# Evaporometer_OnePiece.net
KiCad netlist of a schematic drawn in EAGLE
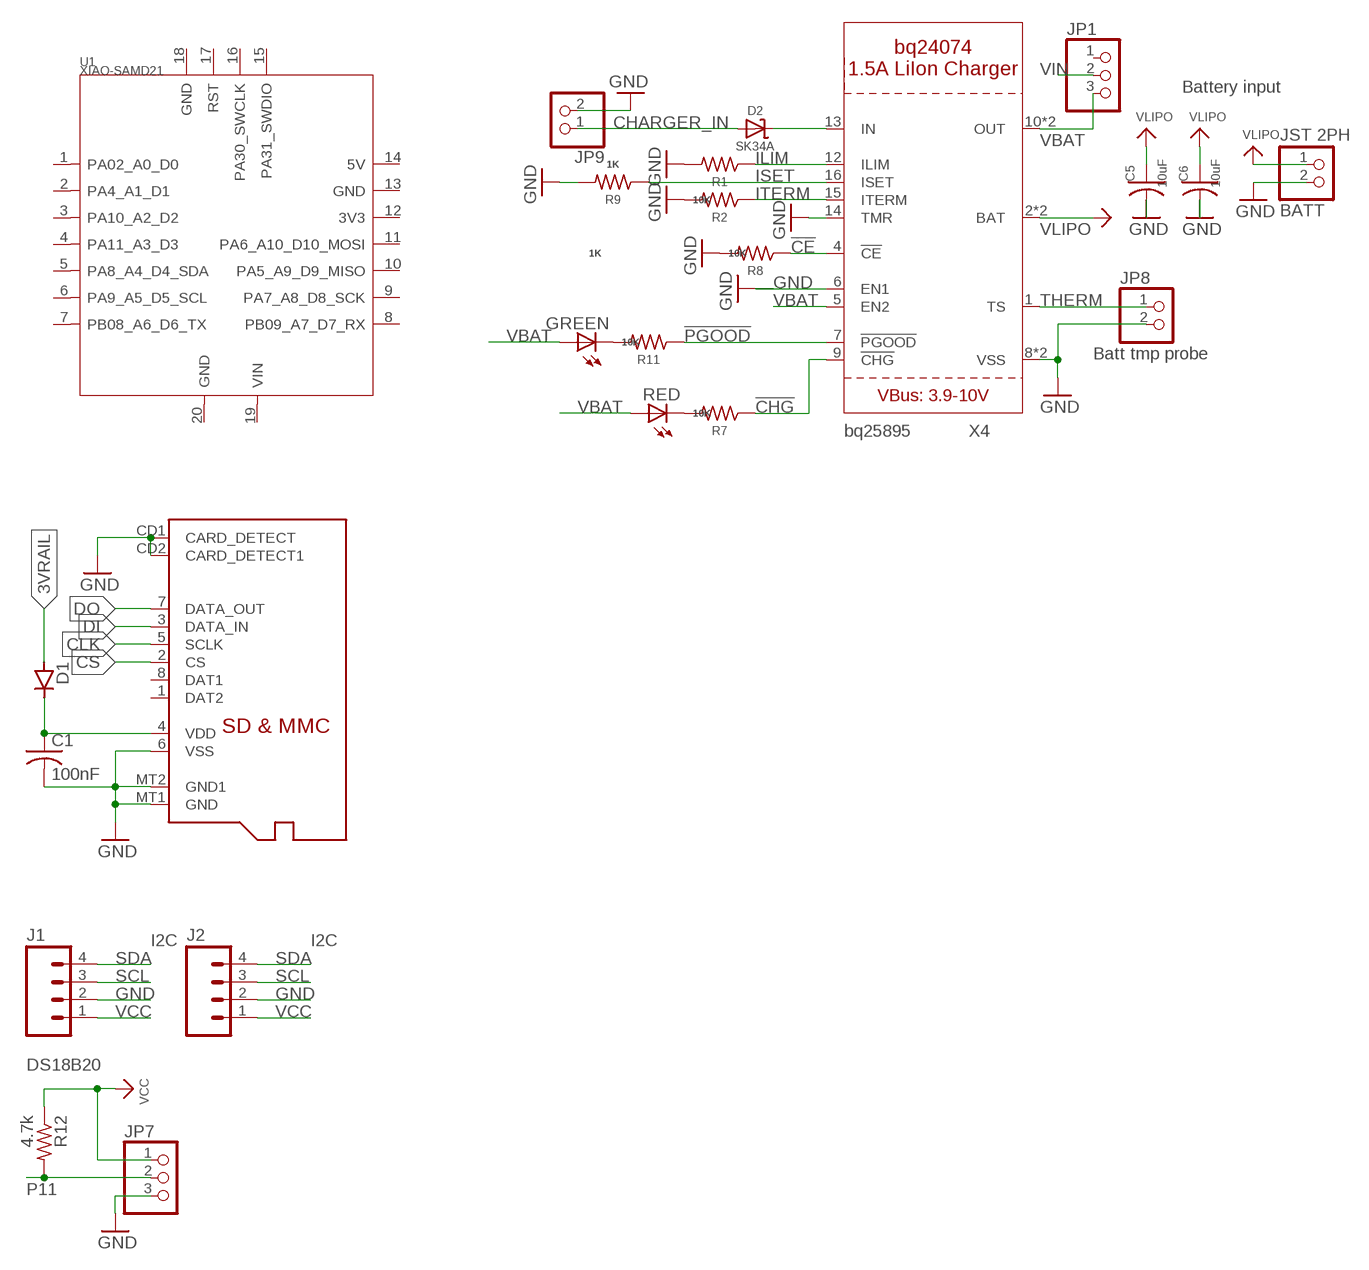
[diagram p0: schematic, sheet 1, part 1 of 2]
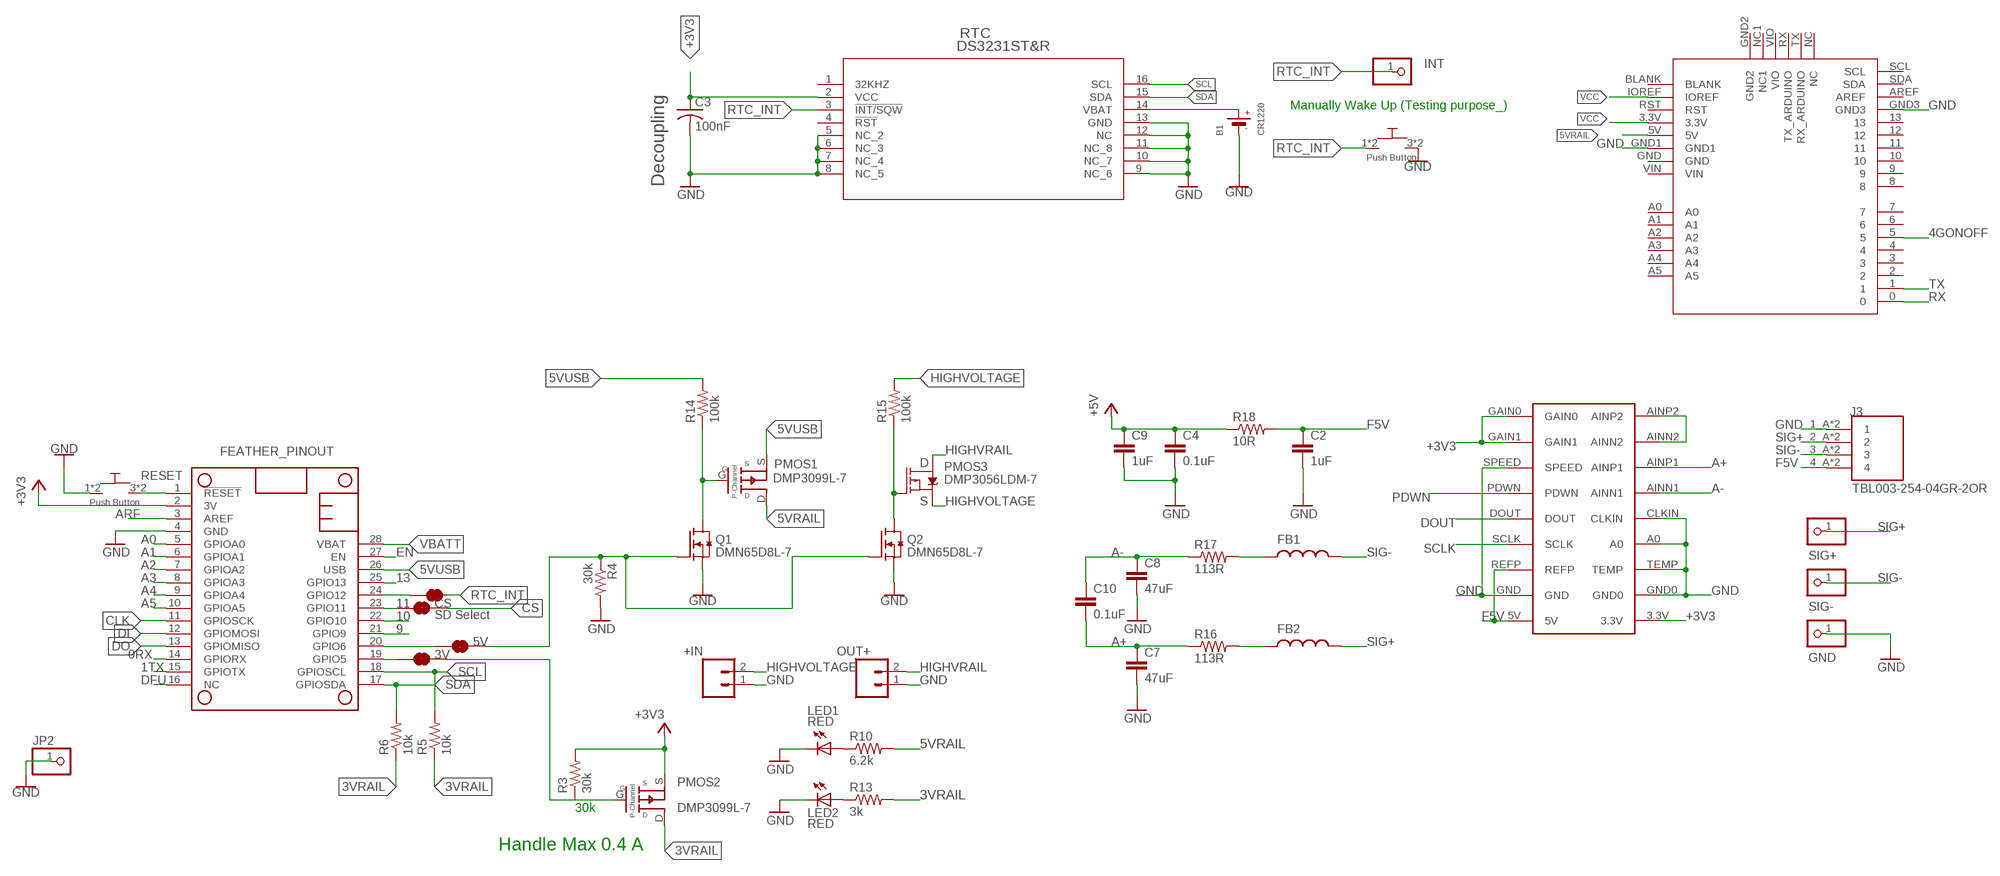
[diagram p1: schematic, sheet 1, part 2 of 2]

(export (version "E")
  (design (tool "Eeschema 10.0.6"))
  (components
    (comp (ref "+IN")
      (value "HIGHV-IN")
      (footprint "eagle-import:1X02_NO_SILK")
      (libsource (lib "eagle-import") (part "CONN_021X02_NO_SILK"))
    )
    (comp (ref "3V")
      (value "JUMPER-SMT_2_NC_TRACE_SILK")
      (footprint "eagle-import:SMT-JUMPER_2_NC_TRACE_SILK")
      (libsource (lib "eagle-import") (part "JUMPER-SMT_2_NC_TRACE_SILK"))
    )
    (comp (ref "5V")
      (value "JUMPER-SMT_2_NC_TRACE_SILK")
      (footprint "eagle-import:SMT-JUMPER_2_NC_TRACE_SILK")
      (libsource (lib "eagle-import") (part "JUMPER-SMT_2_NC_TRACE_SILK"))
    )
    (comp (ref "ADS1232")
      (value "ADS1232")
      (footprint "eagle-import:ADS1232")
      (libsource (lib "eagle-import") (part "ADS1232"))
    )
    (comp (ref "B1")
      (value "CR1220")
      (footprint "eagle-import:CR1220")
      (libsource (lib "eagle-import") (part "BATTERYCR1220_SMT"))
    )
    (comp (ref "BATT")
      (value "JST 2PH")
      (footprint "eagle-import:JST-PH-2-SMT-RA")
      (libsource (lib "eagle-import") (part "JST_2PIN-SMT-RA"))
    )
    (comp (ref "C1")
      (value "100nF")
      (footprint "eagle-import:C1206")
      (libsource (lib "eagle-import") (part "C-USC1206"))
    )
    (comp (ref "C2")
      (value "1uF")
      (footprint "eagle-import:C0805")
      (libsource (lib "eagle-import") (part "C-EUC0805"))
    )
    (comp (ref "C3")
      (value "100nF")
      (footprint "eagle-import:C1206")
      (libsource (lib "eagle-import") (part "C-USC1206"))
    )
    (comp (ref "C4")
      (value "0.1uF")
      (footprint "eagle-import:C0805")
      (libsource (lib "eagle-import") (part "C-EUC0805"))
    )
    (comp (ref "C5")
      (value "10uF")
      (footprint "eagle-import:C0805K")
      (libsource (lib "eagle-import") (part "C-USC0805K"))
    )
    (comp (ref "C6")
      (value "10uF")
      (footprint "eagle-import:C0805K")
      (libsource (lib "eagle-import") (part "C-USC0805K"))
    )
    (comp (ref "C7")
      (value "47uF")
      (footprint "eagle-import:C0805")
      (libsource (lib "eagle-import") (part "C-EUC0805"))
    )
    (comp (ref "C8")
      (value "47uF")
      (footprint "eagle-import:C0805")
      (libsource (lib "eagle-import") (part "C-EUC0805"))
    )
    (comp (ref "C9")
      (value "1uF")
      (footprint "eagle-import:C0805")
      (libsource (lib "eagle-import") (part "C-EUC0805"))
    )
    (comp (ref "C10")
      (value "0.1uF")
      (footprint "eagle-import:C0805")
      (libsource (lib "eagle-import") (part "C-EUC0805"))
    )
    (comp (ref "CS")
      (value "SD Select")
      (footprint "eagle-import:SMT-JUMPER_2_NC_TRACE_SILK")
      (libsource (lib "eagle-import") (part "JUMPER-SMT_2_NC_TRACE_SILK"))
    )
    (comp (ref "D1")
      (value "D-SOD123")
      (footprint "eagle-import:SOD123")
      (libsource (lib "eagle-import") (part "D-SOD123"))
    )
    (comp (ref "D2")
      (value "SK34A")
      (footprint "eagle-import:SMADIODE")
      (libsource (lib "eagle-import") (part "DIODE-SCHOTTKYSMA"))
    )
    (comp (ref "FB1")
      (value "WE-RFI_0805A_744760282A")
      (footprint "eagle-import:WE-RFI_0805A")
      (libsource (lib "eagle-import") (part "WE-RFI_0805A_744760282A"))
    )
    (comp (ref "FB2")
      (value "WE-RFI_0805A_744760282A")
      (footprint "eagle-import:WE-RFI_0805A")
      (libsource (lib "eagle-import") (part "WE-RFI_0805A_744760282A"))
    )
    (comp (ref "GND")
      (value "PINHD-1X1")
      (footprint "eagle-import:1X01")
      (libsource (lib "eagle-import") (part "pinhead_325_PINHD-1X1"))
    )
    (comp (ref "GREEN")
      (value "LEDSMT1206")
      (footprint "eagle-import:1206")
      (libsource (lib "eagle-import") (part "adafruit_420_LEDSMT1206"))
    )
    (comp (ref "INT")
      (value "PINHD-1X1CB")
      (footprint "eagle-import:1X01-CLEANBIG")
      (libsource (lib "eagle-import") (part "PINHD-1X1CB"))
    )
    (comp (ref "J1")
      (value "M04PTH")
      (footprint "eagle-import:1X04")
      (libsource (lib "eagle-import") (part "M04PTH"))
    )
    (comp (ref "J2")
      (value "M04PTH")
      (footprint "eagle-import:1X04")
      (libsource (lib "eagle-import") (part "M04PTH"))
    )
    (comp (ref "J3")
      (value "TBL003-254-04GR-2OR")
      (footprint "eagle-import:CUI_TBL003-254-04GR-2OR")
      (fields (field (name "MF") "CUI Devices"))
      (libsource (lib "eagle-import") (part "TBL003-254-04GR-2OR"))
    )
    (comp (ref "JP1")
      (value "PINHD-1X3")
      (footprint "eagle-import:1X03")
      (libsource (lib "eagle-import") (part "PINHD-1X3"))
    )
    (comp (ref "JP2")
      (value "PINHD-1X1CB")
      (footprint "eagle-import:1X01-CLEANBIG")
      (libsource (lib "eagle-import") (part "PINHD-1X1CB"))
    )
    (comp (ref "JP7")
      (value "PINHD-1X3")
      (footprint "eagle-import:1X03")
      (libsource (lib "eagle-import") (part "PINHD-1X3"))
    )
    (comp (ref "JP8")
      (value "PINHD-1X2")
      (footprint "eagle-import:1X02")
      (libsource (lib "eagle-import") (part "PINHD-1X2"))
    )
    (comp (ref "JP9")
      (value "PINHD-1X2")
      (footprint "eagle-import:1X02")
      (libsource (lib "eagle-import") (part "PINHD-1X2"))
    )
    (comp (ref "LED1")
      (value "RED")
      (footprint "eagle-import:CHIPLED_0805")
      (libsource (lib "eagle-import") (part "LEDCHIPLED_0805"))
    )
    (comp (ref "LED2")
      (value "RED")
      (footprint "eagle-import:CHIPLED_0805")
      (libsource (lib "eagle-import") (part "LEDCHIPLED_0805"))
    )
    (comp (ref "MICROSD")
      (value "MICROSD")
      (footprint "eagle-import:MICROSD")
      (libsource (lib "eagle-import") (part "MICROSD"))
    )
    (comp (ref "MS2")
      (value "FEATHER_PINOUT")
      (footprint "eagle-import:FEATHERWING")
      (libsource (lib "eagle-import") (part "FEATHERWING"))
    )
    (comp (ref "OUT+")
      (value "HIGHV-OUT")
      (footprint "eagle-import:1X02_NO_SILK")
      (libsource (lib "eagle-import") (part "CONN_021X02_NO_SILK"))
    )
    (comp (ref "PMOS1")
      (value "DMP3099L-7")
      (footprint "eagle-import:SOT-23-3")
      (libsource (lib "eagle-import") (part "SSM3J3228R"))
    )
    (comp (ref "PMOS2")
      (value "DMP3099L-7")
      (footprint "eagle-import:SOT-23-3")
      (libsource (lib "eagle-import") (part "SSM3J3228R"))
    )
    (comp (ref "PMOS3")
      (value "DMP3056LDM-7")
      (footprint "eagle-import:SOT23-6")
      (libsource (lib "eagle-import") (part "P-MOSFET"))
    )
    (comp (ref "Q1")
      (value "DMN65D8L-7")
      (footprint "eagle-import:SOT23-S")
      (libsource (lib "eagle-import") (part "NMOS"))
    )
    (comp (ref "Q2")
      (value "DMN65D8L-7")
      (footprint "eagle-import:SOT23-S")
      (libsource (lib "eagle-import") (part "NMOS"))
    )
    (comp (ref "R1")
      (value "1K")
      (footprint "eagle-import:M0805")
      (libsource (lib "eagle-import") (part "R-US_M0805"))
    )
    (comp (ref "R2")
      (value "10K")
      (footprint "eagle-import:M0805")
      (libsource (lib "eagle-import") (part "R-US_M0805"))
    )
    (comp (ref "R3")
      (value "30k")
      (footprint "eagle-import:RES_1206")
      (fields
        (field (name "DIGIKEY_PART_NUMBER") "WSLP-.05TR-ND")
        (field (name "MANUFACTURER") "Vishay Dale")
        (field (name "MPN") "WSLP1206R0500FEA")
        (field (name "CREATED_BY") "PCBLayout.com")
      )
      (libsource (lib "eagle-import") (part "WSLP1206R0500FEA"))
    )
    (comp (ref "R4")
      (value "30k")
      (footprint "eagle-import:RES_1206")
      (fields
        (field (name "DIGIKEY_PART_NUMBER") "WSLP-.05TR-ND")
        (field (name "MANUFACTURER") "Vishay Dale")
        (field (name "MPN") "WSLP1206R0500FEA")
        (field (name "CREATED_BY") "PCBLayout.com")
      )
      (libsource (lib "eagle-import") (part "WSLP1206R0500FEA"))
    )
    (comp (ref "R5")
      (value "10k")
      (footprint "eagle-import:RES_1206")
      (fields
        (field (name "DIGIKEY_PART_NUMBER") "WSLP-.05TR-ND")
        (field (name "MANUFACTURER") "Vishay Dale")
        (field (name "MPN") "WSLP1206R0500FEA")
        (field (name "CREATED_BY") "PCBLayout.com")
      )
      (libsource (lib "eagle-import") (part "WSLP1206R0500FEA"))
    )
    (comp (ref "R6")
      (value "10k")
      (footprint "eagle-import:RES_1206")
      (fields
        (field (name "DIGIKEY_PART_NUMBER") "WSLP-.05TR-ND")
        (field (name "MANUFACTURER") "Vishay Dale")
        (field (name "MPN") "WSLP1206R0500FEA")
        (field (name "CREATED_BY") "PCBLayout.com")
      )
      (libsource (lib "eagle-import") (part "WSLP1206R0500FEA"))
    )
    (comp (ref "R7")
      (value "10K")
      (footprint "eagle-import:M0805")
      (libsource (lib "eagle-import") (part "R-US_M0805"))
    )
    (comp (ref "R8")
      (value "10K")
      (footprint "eagle-import:M0805")
      (libsource (lib "eagle-import") (part "R-US_M0805"))
    )
    (comp (ref "R9")
      (value "1K")
      (footprint "eagle-import:M0805")
      (libsource (lib "eagle-import") (part "R-US_M0805"))
    )
    (comp (ref "R10")
      (value "6.2k")
      (footprint "eagle-import:RES_1206")
      (fields
        (field (name "DIGIKEY_PART_NUMBER") "WSLP-.05TR-ND")
        (field (name "MANUFACTURER") "Vishay Dale")
        (field (name "MPN") "WSLP1206R0500FEA")
        (field (name "CREATED_BY") "PCBLayout.com")
      )
      (libsource (lib "eagle-import") (part "WSLP1206R0500FEA"))
    )
    (comp (ref "R11")
      (value "10K")
      (footprint "eagle-import:M0805")
      (libsource (lib "eagle-import") (part "R-US_M0805"))
    )
    (comp (ref "R12")
      (value "4.7k")
      (footprint "eagle-import:0805-THM")
      (libsource (lib "eagle-import") (part "FLIPFLOP-RES"))
    )
    (comp (ref "R13")
      (value "3k")
      (footprint "eagle-import:RES_1206")
      (fields
        (field (name "DIGIKEY_PART_NUMBER") "WSLP-.05TR-ND")
        (field (name "MANUFACTURER") "Vishay Dale")
        (field (name "MPN") "WSLP1206R0500FEA")
        (field (name "CREATED_BY") "PCBLayout.com")
      )
      (libsource (lib "eagle-import") (part "WSLP1206R0500FEA"))
    )
    (comp (ref "R14")
      (value "100k")
      (footprint "eagle-import:RES_1206")
      (fields
        (field (name "DIGIKEY_PART_NUMBER") "WSLP-.05TR-ND")
        (field (name "MANUFACTURER") "Vishay Dale")
        (field (name "MPN") "WSLP1206R0500FEA")
        (field (name "CREATED_BY") "PCBLayout.com")
      )
      (libsource (lib "eagle-import") (part "WSLP1206R0500FEA"))
    )
    (comp (ref "R15")
      (value "100k")
      (footprint "eagle-import:RES_1206")
      (fields
        (field (name "DIGIKEY_PART_NUMBER") "WSLP-.05TR-ND")
        (field (name "MANUFACTURER") "Vishay Dale")
        (field (name "MPN") "WSLP1206R0500FEA")
        (field (name "CREATED_BY") "PCBLayout.com")
      )
      (libsource (lib "eagle-import") (part "WSLP1206R0500FEA"))
    )
    (comp (ref "R16")
      (value "113R")
      (footprint "eagle-import:R0805")
      (libsource (lib "eagle-import") (part "rcl_334_R-US_R0805"))
    )
    (comp (ref "R17")
      (value "113R")
      (footprint "eagle-import:R0805")
      (libsource (lib "eagle-import") (part "rcl_334_R-US_R0805"))
    )
    (comp (ref "R18")
      (value "10R")
      (footprint "eagle-import:R0805")
      (libsource (lib "eagle-import") (part "rcl_334_R-US_R0805"))
    )
    (comp (ref "RED")
      (value "LEDSMT1206")
      (footprint "eagle-import:1206")
      (libsource (lib "eagle-import") (part "adafruit_420_LEDSMT1206"))
    )
    (comp (ref "RTC")
      (value "DS3231ST&R")
      (footprint "eagle-import:21-0042B_16")
      (fields (field (name "MANUFACTURER_PART_NUMBER") "DS3231S#T&R"))
      (libsource (lib "eagle-import") (part "DS3231ST&R"))
    )
    (comp (ref "RTC_INT")
      (value "JUMPER-SMT_2_NC_TRACE_SILK")
      (footprint "eagle-import:SMT-JUMPER_2_NC_TRACE_SILK")
      (libsource (lib "eagle-import") (part "JUMPER-SMT_2_NC_TRACE_SILK"))
    )
    (comp (ref "SIG+")
      (value "PINHD-1X1")
      (footprint "eagle-import:1X01")
      (libsource (lib "eagle-import") (part "pinhead_325_PINHD-1X1"))
    )
    (comp (ref "SIG-")
      (value "PINHD-1X1")
      (footprint "eagle-import:1X01")
      (libsource (lib "eagle-import") (part "pinhead_325_PINHD-1X1"))
    )
    (comp (ref "U$1")
      (value "PUSH_BUTTON")
      (footprint "eagle-import:PUSHBUTTON_SMD")
      (libsource (lib "eagle-import") (part "PUSH_BUTTON"))
    )
    (comp (ref "U$2")
      (value "LTE_BOARD")
      (footprint "eagle-import:LTE_BOARD_FOOTPRINT")
      (libsource (lib "eagle-import") (part "LTE_BOARD"))
    )
    (comp (ref "U$3")
      (value "PUSH_BUTTON")
      (footprint "eagle-import:PUSHBUTTON_SMD")
      (libsource (lib "eagle-import") (part "PUSH_BUTTON"))
    )
    (comp (ref "U1")
      (value "XIAO-SAMD21")
      (footprint "eagle-import:XIAO-SAMD21_RP2040-MODULE14P-2.54-21X17.8MM")
      (libsource (lib "eagle-import") (part "XIAO-SAMD21"))
    )
    (comp (ref "X4")
      (value "BQ24074")
      (footprint "eagle-import:QFN16_3MM")
      (libsource (lib "eagle-import") (part "BQ24074"))
    )
  )
  (nets
    (net (code "1") (name "+3V3") (class "Default")
      (node (ref "ADS1232") (pin "3.3V") (pinfunction "3.3V_3.3V") (pintype "bidirectional"))
      (node (ref "ADS1232") (pin "GAIN0") (pinfunction "GAIN0_GAIN0") (pintype "bidirectional"))
      (node (ref "ADS1232") (pin "GAIN1") (pinfunction "GAIN1_GAIN1") (pintype "bidirectional"))
      (node (ref "C3") (pin "1") (pinfunction "1_1") (pintype "passive"))
      (node (ref "MS2") (pin "2") (pinfunction "3V_2") (pintype "power_in"))
      (node (ref "PMOS2") (pin "S") (pinfunction "S_S") (pintype "bidirectional"))
      (node (ref "R3") (pin "2") (pinfunction "2_2") (pintype "passive"))
      (node (ref "RTC") (pin "2") (pinfunction "VCC_2") (pintype "power_in"))
    )
    (net (code "2") (name "+5V") (class "Default")
      (node (ref "C4") (pin "1") (pinfunction "1_1") (pintype "passive"))
      (node (ref "C9") (pin "1") (pinfunction "1_1") (pintype "passive"))
      (node (ref "R18") (pin "1") (pinfunction "1_1") (pintype "passive"))
    )
    (net (code "3") (name "/0RX") (class "Default")
      (node (ref "MS2") (pin "14") (pinfunction "GPIORX_14") (pintype "bidirectional"))
    )
    (net (code "4") (name "/1TX") (class "Default")
      (node (ref "MS2") (pin "15") (pinfunction "GPIOTX_15") (pintype "bidirectional"))
    )
    (net (code "5") (name "/4GONOFF") (class "Default")
      (node (ref "U$2") (pin "5") (pinfunction "5_5") (pintype "bidirectional"))
    )
    (net (code "6") (name "/9") (class "Default")
      (node (ref "MS2") (pin "21") (pinfunction "GPIO9_21") (pintype "bidirectional"))
    )
    (net (code "7") (name "/10") (class "Default")
      (node (ref "MS2") (pin "22") (pinfunction "GPIO10_22") (pintype "bidirectional"))
    )
    (net (code "8") (name "/11") (class "Default")
      (node (ref "CS") (pin "1") (pinfunction "1_1") (pintype "passive"))
      (node (ref "MS2") (pin "23") (pinfunction "GPIO11_23") (pintype "bidirectional"))
    )
    (net (code "9") (name "/13") (class "Default")
      (node (ref "MS2") (pin "25") (pinfunction "GPIO13_25") (pintype "bidirectional"))
    )
    (net (code "10") (name "/A+") (class "Default")
      (node (ref "ADS1232") (pin "AINP1") (pinfunction "AINP1_AINP1") (pintype "bidirectional"))
      (node (ref "C10") (pin "2") (pinfunction "2_2") (pintype "passive"))
      (node (ref "C7") (pin "1") (pinfunction "1_1") (pintype "passive"))
      (node (ref "R16") (pin "1") (pinfunction "1_1") (pintype "passive"))
    )
    (net (code "11") (name "/A-") (class "Default")
      (node (ref "ADS1232") (pin "AINN1") (pinfunction "AINN1_AINN1") (pintype "bidirectional"))
      (node (ref "C10") (pin "1") (pinfunction "1_1") (pintype "passive"))
      (node (ref "C8") (pin "1") (pinfunction "1_1") (pintype "passive"))
      (node (ref "R17") (pin "1") (pinfunction "1_1") (pintype "passive"))
    )
    (net (code "12") (name "/A0") (class "Default")
      (node (ref "MS2") (pin "5") (pinfunction "GPIOA0_5") (pintype "bidirectional"))
    )
    (net (code "13") (name "/A1") (class "Default")
      (node (ref "MS2") (pin "6") (pinfunction "GPIOA1_6") (pintype "bidirectional"))
    )
    (net (code "14") (name "/A2") (class "Default")
      (node (ref "MS2") (pin "7") (pinfunction "GPIOA2_7") (pintype "bidirectional"))
    )
    (net (code "15") (name "/A3") (class "Default")
      (node (ref "MS2") (pin "8") (pinfunction "GPIOA3_8") (pintype "bidirectional"))
    )
    (net (code "16") (name "/A4") (class "Default")
      (node (ref "MS2") (pin "9") (pinfunction "GPIOA4_9") (pintype "bidirectional"))
    )
    (net (code "17") (name "/A5") (class "Default")
      (node (ref "MS2") (pin "10") (pinfunction "GPIOA5_10") (pintype "bidirectional"))
    )
    (net (code "18") (name "/ARF") (class "Default")
      (node (ref "MS2") (pin "3") (pinfunction "AREF_3") (pintype "passive"))
    )
    (net (code "19") (name "/CHARGER_IN") (class "Default")
      (node (ref "D2") (pin "A") (pinfunction "A_A") (pintype "passive"))
      (node (ref "JP9") (pin "1") (pinfunction "1_1") (pintype "passive"))
    )
    (net (code "20") (name "/DFU") (class "Default")
      (node (ref "MS2") (pin "16") (pinfunction "NC_16") (pintype "passive"))
    )
    (net (code "21") (name "/DOUT") (class "Default")
      (node (ref "ADS1232") (pin "DOUT") (pinfunction "DOUT_DOUT") (pintype "bidirectional"))
    )
    (net (code "22") (name "/EN") (class "Default")
      (node (ref "MS2") (pin "27") (pinfunction "EN_27") (pintype "passive"))
    )
    (net (code "23") (name "/F5V") (class "Default")
      (node (ref "ADS1232") (pin "5V") (pinfunction "5V_5V") (pintype "bidirectional"))
      (node (ref "ADS1232") (pin "REFP") (pinfunction "REFP_REFP") (pintype "bidirectional"))
      (node (ref "C2") (pin "1") (pinfunction "1_1") (pintype "passive"))
      (node (ref "J3") (pin "4_A") (pinfunction "4_4_A") (pintype "passive"))
      (node (ref "J3") (pin "4_B") (pinfunction "4_4_B") (pintype "passive"))
      (node (ref "R18") (pin "2") (pinfunction "2_2") (pintype "passive"))
    )
    (net (code "24") (name "/HIGHVRAIL") (class "Default")
      (node (ref "OUT+") (pin "2") (pinfunction "2_2") (pintype "passive"))
      (node (ref "PMOS3") (pin "1") (pinfunction "D_1") (pintype "bidirectional"))
      (node (ref "PMOS3") (pin "2") (pinfunction "D_2") (pintype "bidirectional"))
      (node (ref "PMOS3") (pin "5") (pinfunction "D_5") (pintype "bidirectional"))
      (node (ref "PMOS3") (pin "6") (pinfunction "D_6") (pintype "bidirectional"))
    )
    (net (code "25") (name "/ILIM") (class "Default")
      (node (ref "R1") (pin "1") (pinfunction "1_1") (pintype "passive"))
      (node (ref "X4") (pin "12") (pinfunction "ILIM_12") (pintype "input"))
    )
    (net (code "26") (name "/ISET") (class "Default")
      (node (ref "R9") (pin "1") (pinfunction "1_1") (pintype "passive"))
      (node (ref "X4") (pin "16") (pinfunction "ISET_16") (pintype "input"))
    )
    (net (code "27") (name "/ITERM") (class "Default")
      (node (ref "R2") (pin "1") (pinfunction "1_1") (pintype "passive"))
      (node (ref "X4") (pin "15") (pinfunction "ITERM_15") (pintype "input"))
    )
    (net (code "28") (name "/P11") (class "Default")
      (node (ref "JP7") (pin "2") (pinfunction "2_2") (pintype "passive"))
      (node (ref "R12") (pin "2") (pinfunction "2_2") (pintype "passive"))
    )
    (net (code "29") (name "/PDWN") (class "Default")
      (node (ref "ADS1232") (pin "PDWN") (pinfunction "PDWN_PDWN") (pintype "bidirectional"))
    )
    (net (code "30") (name "/RESET") (class "Default")
      (node (ref "MS2") (pin "1") (pinfunction "~{RESET}_1") (pintype "input"))
      (node (ref "U$3") (pin "3") (pinfunction "P$2_3") (pintype "bidirectional"))
      (node (ref "U$3") (pin "4") (pinfunction "P$2_4") (pintype "bidirectional"))
    )
    (net (code "31") (name "/RX") (class "Default")
      (node (ref "U$2") (pin "0") (pinfunction "0_0") (pintype "bidirectional"))
    )
    (net (code "32") (name "/SCLK") (class "Default")
      (node (ref "ADS1232") (pin "SCLK") (pinfunction "SCLK_SCLK") (pintype "bidirectional"))
    )
    (net (code "33") (name "/SIG+") (class "Default")
      (node (ref "FB2") (pin "2") (pinfunction "2_2") (pintype "passive"))
      (node (ref "J3") (pin "2_A") (pinfunction "2_2_A") (pintype "passive"))
      (node (ref "J3") (pin "2_B") (pinfunction "2_2_B") (pintype "passive"))
      (node (ref "SIG+") (pin "1") (pinfunction "1_1") (pintype "passive"))
    )
    (net (code "34") (name "/SIG-") (class "Default")
      (node (ref "FB1") (pin "2") (pinfunction "2_2") (pintype "passive"))
      (node (ref "J3") (pin "3_A") (pinfunction "3_3_A") (pintype "passive"))
      (node (ref "J3") (pin "3_B") (pinfunction "3_3_B") (pintype "passive"))
      (node (ref "SIG-") (pin "1") (pinfunction "1_1") (pintype "passive"))
    )
    (net (code "35") (name "/THERM") (class "Default")
      (node (ref "JP8") (pin "1") (pinfunction "1_1") (pintype "passive"))
      (node (ref "X4") (pin "1") (pinfunction "TS_1") (pintype "input"))
    )
    (net (code "36") (name "/TX") (class "Default")
      (node (ref "U$2") (pin "1") (pinfunction "1_1") (pintype "bidirectional"))
    )
    (net (code "37") (name "/VBAT") (class "Default")
      (node (ref "GREEN") (pin "A") (pinfunction "A_A") (pintype "passive"))
      (node (ref "JP1") (pin "3") (pinfunction "3_3") (pintype "passive"))
      (node (ref "RED") (pin "A") (pinfunction "A_A") (pintype "passive"))
      (node (ref "X4") (pin "10") (pinfunction "OUT_10") (pintype "output"))
      (node (ref "X4") (pin "11") (pinfunction "OUT_11") (pintype "output"))
      (node (ref "X4") (pin "5") (pinfunction "EN2_5") (pintype "input"))
    )
    (net (code "38") (name "/VIN") (class "Default")
      (node (ref "JP1") (pin "2") (pinfunction "2_2") (pintype "passive"))
    )
    (net (code "39") (name "/~{CE}") (class "Default")
      (node (ref "R8") (pin "1") (pinfunction "1_1") (pintype "passive"))
      (node (ref "X4") (pin "4") (pinfunction "~{CE}_4") (pintype "input"))
    )
    (net (code "40") (name "/~{CHG}") (class "Default")
      (node (ref "R7") (pin "1") (pinfunction "1_1") (pintype "passive"))
      (node (ref "X4") (pin "9") (pinfunction "~{CHG}_9") (pintype "output"))
    )
    (net (code "41") (name "/~{PGOOD}") (class "Default")
      (node (ref "R11") (pin "1") (pinfunction "1_1") (pintype "passive"))
      (node (ref "X4") (pin "7") (pinfunction "~{PGOOD}_7") (pintype "output"))
    )
    (net (code "42") (name "3VRAIL") (class "Default")
      (node (ref "D1") (pin "2") (pinfunction "A_2") (pintype "passive"))
      (node (ref "PMOS2") (pin "D") (pinfunction "D_D") (pintype "bidirectional"))
      (node (ref "R13") (pin "2") (pinfunction "2_2") (pintype "passive"))
      (node (ref "R5") (pin "1") (pinfunction "1_1") (pintype "passive"))
      (node (ref "R6") (pin "1") (pinfunction "1_1") (pintype "passive"))
    )
    (net (code "43") (name "5VRAIL") (class "Default")
      (node (ref "PMOS1") (pin "D") (pinfunction "D_D") (pintype "bidirectional"))
      (node (ref "R10") (pin "2") (pinfunction "2_2") (pintype "passive"))
      (node (ref "U$2") (pin "5V") (pinfunction "5V_5V") (pintype "bidirectional"))
    )
    (net (code "44") (name "5VUSB") (class "Default")
      (node (ref "MS2") (pin "26") (pinfunction "USB_26") (pintype "power_in"))
      (node (ref "PMOS1") (pin "S") (pinfunction "S_S") (pintype "bidirectional"))
      (node (ref "R14") (pin "2") (pinfunction "2_2") (pintype "passive"))
    )
    (net (code "45") (name "CLK") (class "Default")
      (node (ref "MICROSD") (pin "5") (pinfunction "SCLK_5") (pintype "input"))
      (node (ref "MS2") (pin "11") (pinfunction "GPIOSCK_11") (pintype "bidirectional"))
    )
    (net (code "46") (name "CS") (class "Default")
      (node (ref "CS") (pin "2") (pinfunction "2_2") (pintype "passive"))
      (node (ref "MICROSD") (pin "2") (pinfunction "CS_2") (pintype "input"))
    )
    (net (code "47") (name "DI") (class "Default")
      (node (ref "MICROSD") (pin "3") (pinfunction "DATA_IN_3") (pintype "input"))
      (node (ref "MS2") (pin "12") (pinfunction "GPIOMOSI_12") (pintype "bidirectional"))
    )
    (net (code "48") (name "DO") (class "Default")
      (node (ref "MICROSD") (pin "7") (pinfunction "DATA_OUT_7") (pintype "output"))
      (node (ref "MS2") (pin "13") (pinfunction "GPIOMISO_13") (pintype "bidirectional"))
    )
    (net (code "49") (name "GND") (class "Default")
      (node (ref "+IN") (pin "1") (pinfunction "1_1") (pintype "passive"))
      (node (ref "ADS1232") (pin "A0") (pinfunction "A0_A0") (pintype "bidirectional"))
      (node (ref "ADS1232") (pin "AINN2") (pinfunction "AINN2_AINN2") (pintype "bidirectional"))
      (node (ref "ADS1232") (pin "AINP2") (pinfunction "AINP2_AINP2") (pintype "bidirectional"))
      (node (ref "ADS1232") (pin "CLKIN") (pinfunction "CLKIN_CLKIN") (pintype "bidirectional"))
      (node (ref "ADS1232") (pin "GND") (pinfunction "GND_GND") (pintype "bidirectional"))
      (node (ref "ADS1232") (pin "GND0") (pinfunction "GND0_GND0") (pintype "bidirectional"))
      (node (ref "ADS1232") (pin "SPEED") (pinfunction "SPEED_SPEED") (pintype "bidirectional"))
      (node (ref "ADS1232") (pin "TEMP") (pinfunction "TEMP_TEMP") (pintype "bidirectional"))
      (node (ref "B1") (pin "-") (pinfunction "-_-") (pintype "passive"))
      (node (ref "BATT") (pin "2") (pinfunction "1_2") (pintype "passive"))
      (node (ref "C1") (pin "2") (pinfunction "2_2") (pintype "passive"))
      (node (ref "C2") (pin "2") (pinfunction "2_2") (pintype "passive"))
      (node (ref "C3") (pin "2") (pinfunction "2_2") (pintype "passive"))
      (node (ref "C4") (pin "2") (pinfunction "2_2") (pintype "passive"))
      (node (ref "C5") (pin "2") (pinfunction "2_2") (pintype "passive"))
      (node (ref "C6") (pin "2") (pinfunction "2_2") (pintype "passive"))
      (node (ref "C7") (pin "2") (pinfunction "2_2") (pintype "passive"))
      (node (ref "C8") (pin "2") (pinfunction "2_2") (pintype "passive"))
      (node (ref "C9") (pin "2") (pinfunction "2_2") (pintype "passive"))
      (node (ref "GND") (pin "1") (pinfunction "1_1") (pintype "passive"))
      (node (ref "J1") (pin "2") (pinfunction "2_2") (pintype "passive"))
      (node (ref "J2") (pin "2") (pinfunction "2_2") (pintype "passive"))
      (node (ref "J3") (pin "1_A") (pinfunction "1_1_A") (pintype "passive"))
      (node (ref "J3") (pin "1_B") (pinfunction "1_1_B") (pintype "passive"))
      (node (ref "JP2") (pin "1") (pinfunction "1_1") (pintype "passive"))
      (node (ref "JP7") (pin "3") (pinfunction "3_3") (pintype "passive"))
      (node (ref "JP8") (pin "2") (pinfunction "2_2") (pintype "passive"))
      (node (ref "JP9") (pin "2") (pinfunction "2_2") (pintype "passive"))
      (node (ref "LED1") (pin "C") (pinfunction "C_C") (pintype "passive"))
      (node (ref "LED2") (pin "C") (pinfunction "C_C") (pintype "passive"))
      (node (ref "MICROSD") (pin "6") (pinfunction "VSS_6") (pintype "power_in"))
      (node (ref "MICROSD") (pin "CD1") (pinfunction "CARD_DETECT_CD1") (pintype "passive"))
      (node (ref "MICROSD") (pin "CD2") (pinfunction "CARD_DETECT1_CD2") (pintype "passive"))
      (node (ref "MICROSD") (pin "MT1") (pinfunction "GND_MT1") (pintype "power_in"))
      (node (ref "MICROSD") (pin "MT2") (pinfunction "GND1_MT2") (pintype "power_in"))
      (node (ref "MS2") (pin "4") (pinfunction "GND_4") (pintype "power_in"))
      (node (ref "OUT+") (pin "1") (pinfunction "1_1") (pintype "passive"))
      (node (ref "Q1") (pin "2") (pinfunction "S_2") (pintype "passive"))
      (node (ref "Q2") (pin "2") (pinfunction "S_2") (pintype "passive"))
      (node (ref "R1") (pin "2") (pinfunction "2_2") (pintype "passive"))
      (node (ref "R2") (pin "2") (pinfunction "2_2") (pintype "passive"))
      (node (ref "R4") (pin "2") (pinfunction "2_2") (pintype "passive"))
      (node (ref "R8") (pin "2") (pinfunction "2_2") (pintype "passive"))
      (node (ref "R9") (pin "2") (pinfunction "2_2") (pintype "passive"))
      (node (ref "RTC") (pin "10") (pinfunction "NC_7_10") (pintype "passive"))
      (node (ref "RTC") (pin "11") (pinfunction "NC_8_11") (pintype "passive"))
      (node (ref "RTC") (pin "12") (pinfunction "NC_12") (pintype "passive"))
      (node (ref "RTC") (pin "13") (pinfunction "GND_13") (pintype "power_in"))
      (node (ref "RTC") (pin "5") (pinfunction "NC_2_5") (pintype "passive"))
      (node (ref "RTC") (pin "6") (pinfunction "NC_3_6") (pintype "passive"))
      (node (ref "RTC") (pin "7") (pinfunction "NC_4_7") (pintype "passive"))
      (node (ref "RTC") (pin "8") (pinfunction "NC_5_8") (pintype "passive"))
      (node (ref "RTC") (pin "9") (pinfunction "NC_6_9") (pintype "passive"))
      (node (ref "U$1") (pin "3") (pinfunction "P$2_3") (pintype "bidirectional"))
      (node (ref "U$1") (pin "4") (pinfunction "P$2_4") (pintype "bidirectional"))
      (node (ref "U$2") (pin "GND1") (pinfunction "GND1_GND1") (pintype "bidirectional"))
      (node (ref "U$2") (pin "GND3") (pinfunction "GND3_GND3") (pintype "bidirectional"))
      (node (ref "U$3") (pin "1") (pinfunction "P$1_1") (pintype "bidirectional"))
      (node (ref "U$3") (pin "2") (pinfunction "P$1_2") (pintype "bidirectional"))
      (node (ref "X4") (pin "14") (pinfunction "TMR_14") (pintype "input"))
      (node (ref "X4") (pin "6") (pinfunction "EN1_6") (pintype "input"))
      (node (ref "X4") (pin "8") (pinfunction "VSS_8") (pintype "power_in"))
      (node (ref "X4") (pin "THERMAL") (pinfunction "VSS_THERMAL") (pintype "power_in"))
    )
    (net (code "50") (name "HIGHVOLTAGE") (class "Default")
      (node (ref "+IN") (pin "2") (pinfunction "2_2") (pintype "passive"))
      (node (ref "PMOS3") (pin "4") (pinfunction "S_4") (pintype "bidirectional"))
      (node (ref "R15") (pin "2") (pinfunction "2_2") (pintype "passive"))
    )
    (net (code "51") (name "Net-(3V-Pad2)") (class "Default")
      (node (ref "3V") (pin "2") (pinfunction "2_2") (pintype "passive"))
      (node (ref "PMOS2") (pin "G") (pinfunction "G_G") (pintype "bidirectional"))
      (node (ref "R3") (pin "1") (pinfunction "1_1") (pintype "passive"))
    )
    (net (code "52") (name "Net-(B1-+)") (class "Default")
      (node (ref "B1") (pin "+$1") (pinfunction "+_+$1") (pintype "passive"))
      (node (ref "RTC") (pin "14") (pinfunction "VBAT_14") (pintype "power_in"))
    )
    (net (code "53") (name "Net-(D1-C)") (class "Default")
      (node (ref "C1") (pin "1") (pinfunction "1_1") (pintype "passive"))
      (node (ref "D1") (pin "1") (pinfunction "C_1") (pintype "passive"))
      (node (ref "MICROSD") (pin "4") (pinfunction "VDD_4") (pintype "power_in"))
    )
    (net (code "54") (name "Net-(FB1-Pad1)") (class "Default")
      (node (ref "FB1") (pin "1") (pinfunction "1_1") (pintype "passive"))
      (node (ref "R17") (pin "2") (pinfunction "2_2") (pintype "passive"))
    )
    (net (code "55") (name "Net-(FB2-Pad1)") (class "Default")
      (node (ref "FB2") (pin "1") (pinfunction "1_1") (pintype "passive"))
      (node (ref "R16") (pin "2") (pinfunction "2_2") (pintype "passive"))
    )
    (net (code "56") (name "Net-(GREEN-PadC)") (class "Default")
      (node (ref "GREEN") (pin "C") (pinfunction "C_C") (pintype "passive"))
      (node (ref "R11") (pin "2") (pinfunction "2_2") (pintype "passive"))
    )
    (net (code "57") (name "Net-(LED1-PadA)") (class "Default")
      (node (ref "LED1") (pin "A") (pinfunction "A_A") (pintype "passive"))
      (node (ref "R10") (pin "1") (pinfunction "1_1") (pintype "passive"))
    )
    (net (code "58") (name "Net-(LED2-PadA)") (class "Default")
      (node (ref "LED2") (pin "A") (pinfunction "A_A") (pintype "passive"))
      (node (ref "R13") (pin "1") (pinfunction "1_1") (pintype "passive"))
    )
    (net (code "59") (name "Net-(MS2-GPIO5)") (class "Default")
      (node (ref "3V") (pin "1") (pinfunction "1_1") (pintype "passive"))
      (node (ref "MS2") (pin "19") (pinfunction "GPIO5_19") (pintype "bidirectional"))
    )
    (net (code "60") (name "Net-(MS2-GPIO6)") (class "Default")
      (node (ref "5V") (pin "1") (pinfunction "1_1") (pintype "passive"))
      (node (ref "MS2") (pin "20") (pinfunction "GPIO6_20") (pintype "bidirectional"))
    )
    (net (code "61") (name "Net-(MS2-GPIO12)") (class "Default")
      (node (ref "MS2") (pin "24") (pinfunction "GPIO12_24") (pintype "bidirectional"))
      (node (ref "RTC_INT") (pin "1") (pinfunction "1_1") (pintype "passive"))
    )
    (net (code "62") (name "Net-(PMOS3-G)") (class "Default")
      (node (ref "PMOS3") (pin "3") (pinfunction "G_3") (pintype "bidirectional"))
      (node (ref "Q2") (pin "3") (pinfunction "D_3") (pintype "passive"))
      (node (ref "R15") (pin "1") (pinfunction "1_1") (pintype "passive"))
    )
    (net (code "63") (name "Net-(Q1-D)") (class "Default")
      (node (ref "PMOS1") (pin "G") (pinfunction "G_G") (pintype "bidirectional"))
      (node (ref "Q1") (pin "3") (pinfunction "D_3") (pintype "passive"))
      (node (ref "R14") (pin "1") (pinfunction "1_1") (pintype "passive"))
    )
    (net (code "64") (name "Net-(Q1-G)") (class "Default")
      (node (ref "5V") (pin "2") (pinfunction "2_2") (pintype "passive"))
      (node (ref "Q1") (pin "1") (pinfunction "G_1") (pintype "passive"))
      (node (ref "Q2") (pin "1") (pinfunction "G_1") (pintype "passive"))
      (node (ref "R4") (pin "1") (pinfunction "1_1") (pintype "passive"))
    )
    (net (code "65") (name "Net-(R7-Pad2)") (class "Default")
      (node (ref "R7") (pin "2") (pinfunction "2_2") (pintype "passive"))
      (node (ref "RED") (pin "C") (pinfunction "C_C") (pintype "passive"))
    )
    (net (code "66") (name "Net-(X4-IN)") (class "Default")
      (node (ref "D2") (pin "C") (pinfunction "C_C") (pintype "passive"))
      (node (ref "X4") (pin "13") (pinfunction "IN_13") (pintype "power_in"))
    )
    (net (code "67") (name "RTC_INT") (class "Default")
      (node (ref "INT") (pin "1") (pinfunction "1_1") (pintype "passive"))
      (node (ref "RTC") (pin "3") (pinfunction "~{INT/SQW}_3") (pintype "passive"))
      (node (ref "RTC_INT") (pin "2") (pinfunction "2_2") (pintype "passive"))
      (node (ref "U$1") (pin "1") (pinfunction "P$1_1") (pintype "bidirectional"))
      (node (ref "U$1") (pin "2") (pinfunction "P$1_2") (pintype "bidirectional"))
    )
    (net (code "68") (name "SCL") (class "Default")
      (node (ref "J1") (pin "3") (pinfunction "3_3") (pintype "passive"))
      (node (ref "J2") (pin "3") (pinfunction "3_3") (pintype "passive"))
      (node (ref "MS2") (pin "18") (pinfunction "GPIOSCL_18") (pintype "bidirectional"))
      (node (ref "R5") (pin "2") (pinfunction "2_2") (pintype "passive"))
      (node (ref "RTC") (pin "16") (pinfunction "SCL_16") (pintype "passive"))
    )
    (net (code "69") (name "SDA") (class "Default")
      (node (ref "J1") (pin "4") (pinfunction "4_4") (pintype "passive"))
      (node (ref "J2") (pin "4") (pinfunction "4_4") (pintype "passive"))
      (node (ref "MS2") (pin "17") (pinfunction "GPIOSDA_17") (pintype "bidirectional"))
      (node (ref "R6") (pin "2") (pinfunction "2_2") (pintype "passive"))
      (node (ref "RTC") (pin "15") (pinfunction "SDA_15") (pintype "passive"))
    )
    (net (code "70") (name "VBATT") (class "Default")
      (node (ref "MS2") (pin "28") (pinfunction "VBAT_28") (pintype "power_in"))
    )
    (net (code "71") (name "VCC") (class "Default")
      (node (ref "J1") (pin "1") (pinfunction "1_1") (pintype "passive"))
      (node (ref "J2") (pin "1") (pinfunction "1_1") (pintype "passive"))
      (node (ref "JP7") (pin "1") (pinfunction "1_1") (pintype "passive"))
      (node (ref "R12") (pin "1") (pinfunction "1_1") (pintype "passive"))
      (node (ref "U$2") (pin "3.3V") (pinfunction "3.3V_3.3V") (pintype "bidirectional"))
      (node (ref "U$2") (pin "IOREF") (pinfunction "IOREF_IOREF") (pintype "bidirectional"))
    )
    (net (code "72") (name "VLIPO") (class "Default")
      (node (ref "BATT") (pin "1") (pinfunction "2_1") (pintype "passive"))
      (node (ref "C5") (pin "1") (pinfunction "1_1") (pintype "passive"))
      (node (ref "C6") (pin "1") (pinfunction "1_1") (pintype "passive"))
      (node (ref "X4") (pin "2") (pinfunction "BAT_2") (pintype "input"))
      (node (ref "X4") (pin "3") (pinfunction "BAT_3") (pintype "input"))
    )
    (net (code "73") (name "unconnected-(JP1-Pad1)") (class "Default")
      (node (ref "JP1") (pin "1") (pinfunction "1_1") (pintype "passive"))
    )
    (net (code "74") (name "unconnected-(MICROSD-DAT1-Pad8)") (class "Default")
      (node (ref "MICROSD") (pin "8") (pinfunction "DAT1_8") (pintype "bidirectional"))
    )
    (net (code "75") (name "unconnected-(MICROSD-DAT2-Pad1)") (class "Default")
      (node (ref "MICROSD") (pin "1") (pinfunction "DAT2_1") (pintype "bidirectional"))
    )
    (net (code "76") (name "unconnected-(RTC-32KHZ-Pad1)") (class "Default")
      (node (ref "RTC") (pin "1") (pinfunction "32KHZ_1") (pintype "passive"))
    )
    (net (code "77") (name "unconnected-(RTC-~{RST}-Pad4)") (class "Default")
      (node (ref "RTC") (pin "4") (pinfunction "~{RST}_4") (pintype "passive"))
    )
    (net (code "78") (name "unconnected-(U$2-Pad2)") (class "Default")
      (node (ref "U$2") (pin "2") (pinfunction "2_2") (pintype "bidirectional"))
    )
    (net (code "79") (name "unconnected-(U$2-Pad3)") (class "Default")
      (node (ref "U$2") (pin "3") (pinfunction "3_3") (pintype "bidirectional"))
    )
    (net (code "80") (name "unconnected-(U$2-Pad4)") (class "Default")
      (node (ref "U$2") (pin "4") (pinfunction "4_4") (pintype "bidirectional"))
    )
    (net (code "81") (name "unconnected-(U$2-Pad6)") (class "Default")
      (node (ref "U$2") (pin "6") (pinfunction "6_6") (pintype "bidirectional"))
    )
    (net (code "82") (name "unconnected-(U$2-Pad7)") (class "Default")
      (node (ref "U$2") (pin "7") (pinfunction "7_7") (pintype "bidirectional"))
    )
    (net (code "83") (name "unconnected-(U$2-Pad8)") (class "Default")
      (node (ref "U$2") (pin "8") (pinfunction "8_8") (pintype "bidirectional"))
    )
    (net (code "84") (name "unconnected-(U$2-Pad9)") (class "Default")
      (node (ref "U$2") (pin "9") (pinfunction "9_9") (pintype "bidirectional"))
    )
    (net (code "85") (name "unconnected-(U$2-Pad10)") (class "Default")
      (node (ref "U$2") (pin "10") (pinfunction "10_10") (pintype "bidirectional"))
    )
    (net (code "86") (name "unconnected-(U$2-Pad11)") (class "Default")
      (node (ref "U$2") (pin "11") (pinfunction "11_11") (pintype "bidirectional"))
    )
    (net (code "87") (name "unconnected-(U$2-Pad12)") (class "Default")
      (node (ref "U$2") (pin "12") (pinfunction "12_12") (pintype "bidirectional"))
    )
    (net (code "88") (name "unconnected-(U$2-Pad13)") (class "Default")
      (node (ref "U$2") (pin "13") (pinfunction "13_13") (pintype "bidirectional"))
    )
    (net (code "89") (name "unconnected-(U$2-PadA0)") (class "Default")
      (node (ref "U$2") (pin "A0") (pinfunction "A0_A0") (pintype "bidirectional"))
    )
    (net (code "90") (name "unconnected-(U$2-PadA1)") (class "Default")
      (node (ref "U$2") (pin "A1") (pinfunction "A1_A1") (pintype "bidirectional"))
    )
    (net (code "91") (name "unconnected-(U$2-PadA2)") (class "Default")
      (node (ref "U$2") (pin "A2") (pinfunction "A2_A2") (pintype "bidirectional"))
    )
    (net (code "92") (name "unconnected-(U$2-PadA3)") (class "Default")
      (node (ref "U$2") (pin "A3") (pinfunction "A3_A3") (pintype "bidirectional"))
    )
    (net (code "93") (name "unconnected-(U$2-PadA4)") (class "Default")
      (node (ref "U$2") (pin "A4") (pinfunction "A4_A4") (pintype "bidirectional"))
    )
    (net (code "94") (name "unconnected-(U$2-PadA5)") (class "Default")
      (node (ref "U$2") (pin "A5") (pinfunction "A5_A5") (pintype "bidirectional"))
    )
    (net (code "95") (name "unconnected-(U$2-PadAREF)") (class "Default")
      (node (ref "U$2") (pin "AREF") (pinfunction "AREF_AREF") (pintype "bidirectional"))
    )
    (net (code "96") (name "unconnected-(U$2-PadBLANK)") (class "Default")
      (node (ref "U$2") (pin "BLANK") (pinfunction "BLANK_BLANK") (pintype "bidirectional"))
    )
    (net (code "97") (name "unconnected-(U$2-PadGND)") (class "Default")
      (node (ref "U$2") (pin "GND") (pinfunction "GND_GND") (pintype "bidirectional"))
    )
    (net (code "98") (name "unconnected-(U$2-PadGND2)") (class "Default")
      (node (ref "U$2") (pin "GND2") (pinfunction "GND2_GND2") (pintype "bidirectional"))
    )
    (net (code "99") (name "unconnected-(U$2-PadNC)") (class "Default")
      (node (ref "U$2") (pin "NC") (pinfunction "NC_NC") (pintype "bidirectional"))
    )
    (net (code "100") (name "unconnected-(U$2-PadNC1)") (class "Default")
      (node (ref "U$2") (pin "NC1") (pinfunction "NC1_NC1") (pintype "bidirectional"))
    )
    (net (code "101") (name "unconnected-(U$2-PadRST)") (class "Default")
      (node (ref "U$2") (pin "RST") (pinfunction "RST_RST") (pintype "bidirectional"))
    )
    (net (code "102") (name "unconnected-(U$2-PadSCL)") (class "Default")
      (node (ref "U$2") (pin "SCL") (pinfunction "SCL_SCL") (pintype "bidirectional"))
    )
    (net (code "103") (name "unconnected-(U$2-PadSDA)") (class "Default")
      (node (ref "U$2") (pin "SDA") (pinfunction "SDA_SDA") (pintype "bidirectional"))
    )
    (net (code "104") (name "unconnected-(U$2-PadVIN)") (class "Default")
      (node (ref "U$2") (pin "VIN") (pinfunction "VIN_VIN") (pintype "bidirectional"))
    )
    (net (code "105") (name "unconnected-(U$2-PadVIO)") (class "Default")
      (node (ref "U$2") (pin "VIO") (pinfunction "VIO_VIO") (pintype "bidirectional"))
    )
    (net (code "106") (name "unconnected-(U$2-RX_ARDUINO-PadTX)") (class "Default")
      (node (ref "U$2") (pin "TX") (pinfunction "RX_ARDUINO_TX") (pintype "bidirectional"))
    )
    (net (code "107") (name "unconnected-(U$2-TX_ARDUINO-PadRX)") (class "Default")
      (node (ref "U$2") (pin "RX") (pinfunction "TX_ARDUINO_RX") (pintype "bidirectional"))
    )
    (net (code "108") (name "unconnected-(U1-3V3-Pad12)") (class "Default")
      (node (ref "U1") (pin "12") (pinfunction "3V3_12") (pintype "bidirectional"))
    )
    (net (code "109") (name "unconnected-(U1-5V-Pad14)") (class "Default")
      (node (ref "U1") (pin "14") (pinfunction "5V_14") (pintype "bidirectional"))
    )
    (net (code "110") (name "unconnected-(U1-GND-Pad13)") (class "Default")
      (node (ref "U1") (pin "13") (pinfunction "GND_13") (pintype "bidirectional"))
    )
    (net (code "111") (name "unconnected-(U1-GND-Pad18)") (class "Default")
      (node (ref "U1") (pin "18") (pinfunction "GND_18") (pintype "bidirectional"))
    )
    (net (code "112") (name "unconnected-(U1-GND-Pad20)") (class "Default")
      (node (ref "U1") (pin "20") (pinfunction "GND_20") (pintype "bidirectional"))
    )
    (net (code "113") (name "unconnected-(U1-PA02_A0_D0-Pad1)") (class "Default")
      (node (ref "U1") (pin "1") (pinfunction "PA02_A0_D0_1") (pintype "bidirectional"))
    )
    (net (code "114") (name "unconnected-(U1-PA4_A1_D1-Pad2)") (class "Default")
      (node (ref "U1") (pin "2") (pinfunction "PA4_A1_D1_2") (pintype "bidirectional"))
    )
    (net (code "115") (name "unconnected-(U1-PA5_A9_D9_MISO-Pad10)") (class "Default")
      (node (ref "U1") (pin "10") (pinfunction "PA5_A9_D9_MISO_10") (pintype "bidirectional"))
    )
    (net (code "116") (name "unconnected-(U1-PA6_A10_D10_MOSI-Pad11)") (class "Default")
      (node (ref "U1") (pin "11") (pinfunction "PA6_A10_D10_MOSI_11") (pintype "bidirectional"))
    )
    (net (code "117") (name "unconnected-(U1-PA7_A8_D8_SCK-Pad9)") (class "Default")
      (node (ref "U1") (pin "9") (pinfunction "PA7_A8_D8_SCK_9") (pintype "bidirectional"))
    )
    (net (code "118") (name "unconnected-(U1-PA8_A4_D4_SDA-Pad5)") (class "Default")
      (node (ref "U1") (pin "5") (pinfunction "PA8_A4_D4_SDA_5") (pintype "bidirectional"))
    )
    (net (code "119") (name "unconnected-(U1-PA9_A5_D5_SCL-Pad6)") (class "Default")
      (node (ref "U1") (pin "6") (pinfunction "PA9_A5_D5_SCL_6") (pintype "bidirectional"))
    )
    (net (code "120") (name "unconnected-(U1-PA10_A2_D2-Pad3)") (class "Default")
      (node (ref "U1") (pin "3") (pinfunction "PA10_A2_D2_3") (pintype "bidirectional"))
    )
    (net (code "121") (name "unconnected-(U1-PA11_A3_D3-Pad4)") (class "Default")
      (node (ref "U1") (pin "4") (pinfunction "PA11_A3_D3_4") (pintype "bidirectional"))
    )
    (net (code "122") (name "unconnected-(U1-PA30_SWCLK-Pad16)") (class "Default")
      (node (ref "U1") (pin "16") (pinfunction "PA30_SWCLK_16") (pintype "bidirectional"))
    )
    (net (code "123") (name "unconnected-(U1-PA31_SWDIO-Pad15)") (class "Default")
      (node (ref "U1") (pin "15") (pinfunction "PA31_SWDIO_15") (pintype "bidirectional"))
    )
    (net (code "124") (name "unconnected-(U1-PB08_A6_D6_TX-Pad7)") (class "Default")
      (node (ref "U1") (pin "7") (pinfunction "PB08_A6_D6_TX_7") (pintype "bidirectional"))
    )
    (net (code "125") (name "unconnected-(U1-PB09_A7_D7_RX-Pad8)") (class "Default")
      (node (ref "U1") (pin "8") (pinfunction "PB09_A7_D7_RX_8") (pintype "bidirectional"))
    )
    (net (code "126") (name "unconnected-(U1-RST-Pad17)") (class "Default")
      (node (ref "U1") (pin "17") (pinfunction "RST_17") (pintype "bidirectional"))
    )
    (net (code "127") (name "unconnected-(U1-VIN-Pad19)") (class "Default")
      (node (ref "U1") (pin "19") (pinfunction "VIN_19") (pintype "bidirectional"))
    )
  )
)
